# mobo_v1_1_6-20-18.net
KiCad netlist of a schematic drawn in EAGLE
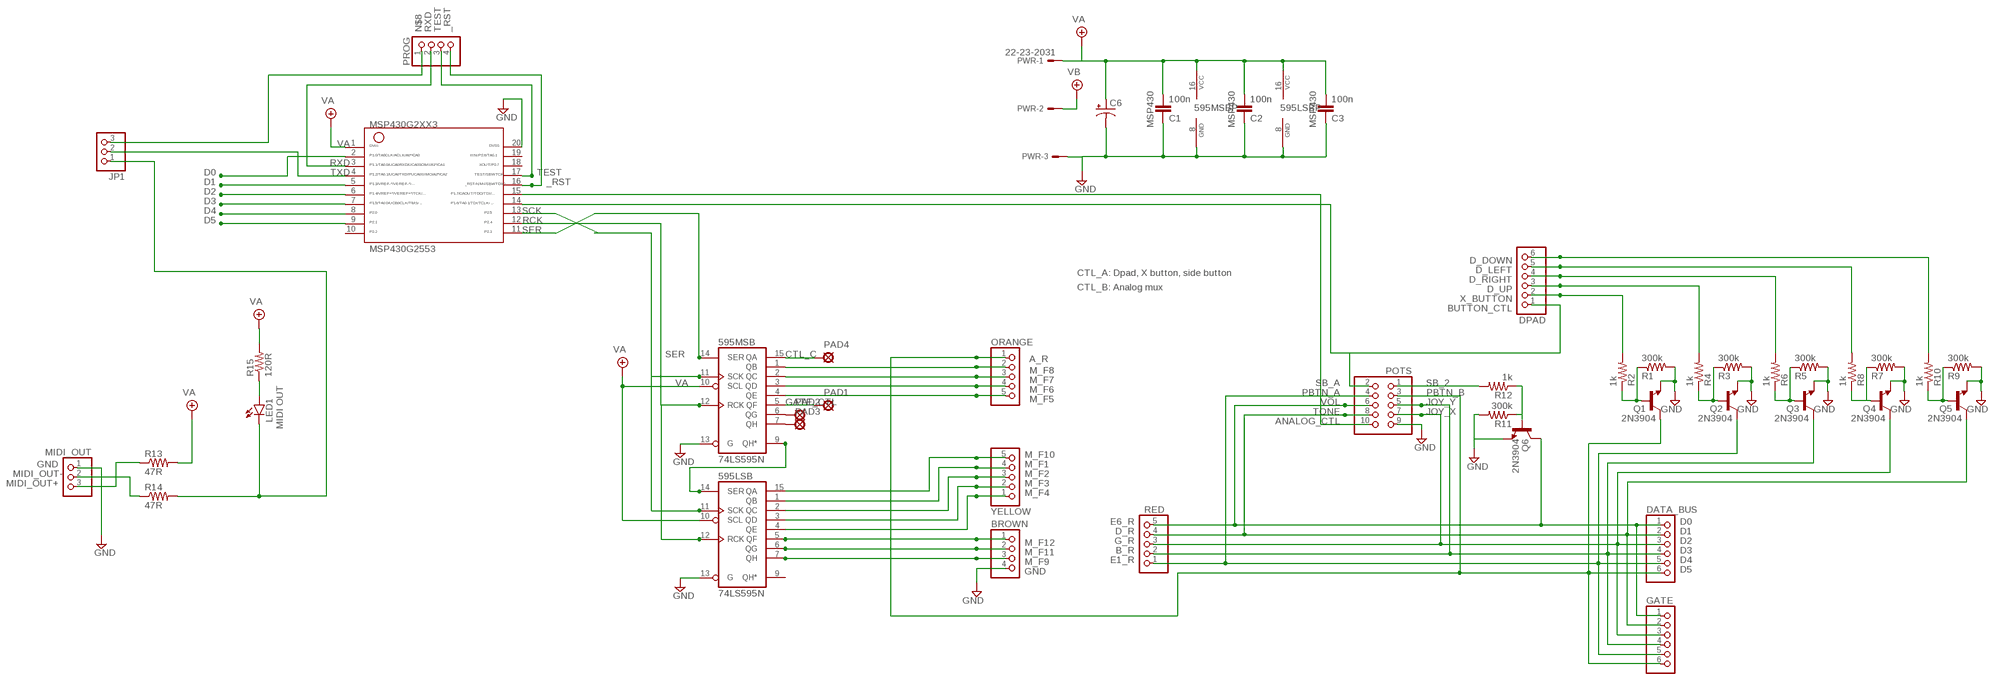
[diagram p0: schematic, sheet 1]

(export (version "E")
  (design (tool "Eeschema 10.0.6"))
  (components
    (comp (ref "595LSB")
      (value "74LS595N")
      (footprint "eagle-import:DIL16")
      (libsource (lib "eagle-import") (part "74595NLS"))
    )
    (comp (ref "595MSB")
      (value "74LS595N")
      (footprint "eagle-import:DIL16")
      (libsource (lib "eagle-import") (part "74595NLS"))
    )
    (comp (ref "BROWN")
      (value "PINHD-1X4")
      (footprint "eagle-import:1X04")
      (libsource (lib "eagle-import") (part "PINHD-1X4"))
    )
    (comp (ref "C1")
      (value "100n")
      (footprint "eagle-import:050X030_050_3")
      (libsource (lib "eagle-import") (part "050X030_050"))
    )
    (comp (ref "C2")
      (value "100n")
      (footprint "eagle-import:050X030_050_3")
      (libsource (lib "eagle-import") (part "050X030_050"))
    )
    (comp (ref "C3")
      (value "100n")
      (footprint "eagle-import:050X030_050_3")
      (libsource (lib "eagle-import") (part "050X030_050"))
    )
    (comp (ref "C6")
      (value "0501")
      (footprint "eagle-import:050_020_1")
      (libsource (lib "eagle-import") (part "0501"))
    )
    (comp (ref "DATA_BUS")
      (value "PINHD-1X6")
      (footprint "eagle-import:1X06")
      (libsource (lib "eagle-import") (part "PINHD-1X6"))
    )
    (comp (ref "DPAD")
      (value "PINHD-1X6")
      (footprint "eagle-import:1X06")
      (libsource (lib "eagle-import") (part "PINHD-1X6"))
    )
    (comp (ref "GATE")
      (value "PINHD-1X6")
      (footprint "eagle-import:1X06")
      (libsource (lib "eagle-import") (part "PINHD-1X6"))
    )
    (comp (ref "JP1")
      (value "PINHD-1X3")
      (footprint "eagle-import:1X03")
      (libsource (lib "eagle-import") (part "PINHD-1X3"))
    )
    (comp (ref "LED1")
      (value "LED3MM")
      (footprint "eagle-import:LED3MM")
      (libsource (lib "eagle-import") (part "LED3MM"))
    )
    (comp (ref "MIDI_OUT")
      (value "PINHD-1X3")
      (footprint "eagle-import:1X03")
      (libsource (lib "eagle-import") (part "PINHD-1X3"))
    )
    (comp (ref "MSP430G2553")
      (value "G2XX3---N20")
      (footprint "eagle-import:N20")
      (libsource (lib "eagle-import") (part "G2XX3---N20"))
    )
    (comp (ref "ORANGE")
      (value "PINHD-1X5")
      (footprint "eagle-import:1X05")
      (libsource (lib "eagle-import") (part "PINHD-1X5"))
    )
    (comp (ref "PAD1")
      (value "PAD")
      (footprint "eagle-import:SQUARE")
      (libsource (lib "eagle-import") (part "PAD"))
    )
    (comp (ref "PAD2")
      (value "PAD")
      (footprint "eagle-import:SQUARE")
      (libsource (lib "eagle-import") (part "PAD"))
    )
    (comp (ref "PAD3")
      (value "PAD")
      (footprint "eagle-import:SQUARE")
      (libsource (lib "eagle-import") (part "PAD"))
    )
    (comp (ref "PAD4")
      (value "PAD")
      (footprint "eagle-import:SQUARE")
      (libsource (lib "eagle-import") (part "PAD"))
    )
    (comp (ref "POTS")
      (value "PINHD-2X5")
      (footprint "eagle-import:2X05")
      (libsource (lib "eagle-import") (part "PINHD-2X5"))
    )
    (comp (ref "PROG")
      (value "PINHD-1X4")
      (footprint "eagle-import:1X04")
      (libsource (lib "eagle-import") (part "PINHD-1X4"))
    )
    (comp (ref "PWR")
      (value "22-23-2031")
      (footprint "eagle-import:22-23-2031")
      (fields (field (name "MF") "MOLEX"))
      (libsource (lib "eagle-import") (part "22-23-2031"))
    )
    (comp (ref "Q1")
      (value "2N3904")
      (footprint "eagle-import:TO92-")
      (libsource (lib "eagle-import") (part "2N3904"))
    )
    (comp (ref "Q2")
      (value "2N3904")
      (footprint "eagle-import:TO92-")
      (libsource (lib "eagle-import") (part "2N3904"))
    )
    (comp (ref "Q3")
      (value "2N3904")
      (footprint "eagle-import:TO92-")
      (libsource (lib "eagle-import") (part "2N3904"))
    )
    (comp (ref "Q4")
      (value "2N3904")
      (footprint "eagle-import:TO92-")
      (libsource (lib "eagle-import") (part "2N3904"))
    )
    (comp (ref "Q5")
      (value "2N3904")
      (footprint "eagle-import:TO92-")
      (libsource (lib "eagle-import") (part "2N3904"))
    )
    (comp (ref "Q6")
      (value "2N3904")
      (footprint "eagle-import:TO92-")
      (libsource (lib "eagle-import") (part "2N3904"))
    )
    (comp (ref "R1")
      (value "300k")
      (footprint "eagle-import:R0207_3")
      (libsource (lib "eagle-import") (part "6MM.3"))
    )
    (comp (ref "R2")
      (value "1k")
      (footprint "eagle-import:R0207_3")
      (libsource (lib "eagle-import") (part "6MM.3"))
    )
    (comp (ref "R3")
      (value "300k")
      (footprint "eagle-import:R0207_3")
      (libsource (lib "eagle-import") (part "6MM.3"))
    )
    (comp (ref "R4")
      (value "1k")
      (footprint "eagle-import:R0207_3")
      (libsource (lib "eagle-import") (part "6MM.3"))
    )
    (comp (ref "R5")
      (value "300k")
      (footprint "eagle-import:R0207_3")
      (libsource (lib "eagle-import") (part "6MM.3"))
    )
    (comp (ref "R6")
      (value "1k")
      (footprint "eagle-import:R0207_3")
      (libsource (lib "eagle-import") (part "6MM.3"))
    )
    (comp (ref "R7")
      (value "300k")
      (footprint "eagle-import:R0207_3")
      (libsource (lib "eagle-import") (part "6MM.3"))
    )
    (comp (ref "R8")
      (value "1k")
      (footprint "eagle-import:R0207_3")
      (libsource (lib "eagle-import") (part "6MM.3"))
    )
    (comp (ref "R9")
      (value "300k")
      (footprint "eagle-import:R0207_3")
      (libsource (lib "eagle-import") (part "6MM.3"))
    )
    (comp (ref "R10")
      (value "1k")
      (footprint "eagle-import:R0207_3")
      (libsource (lib "eagle-import") (part "6MM.3"))
    )
    (comp (ref "R11")
      (value "300k")
      (footprint "eagle-import:R0207_3")
      (libsource (lib "eagle-import") (part "6MM.3"))
    )
    (comp (ref "R12")
      (value "1k")
      (footprint "eagle-import:R0207_3")
      (libsource (lib "eagle-import") (part "6MM.3"))
    )
    (comp (ref "R13")
      (value "47R")
      (footprint "eagle-import:R0207_3")
      (libsource (lib "eagle-import") (part "6MM.3"))
    )
    (comp (ref "R14")
      (value "47R")
      (footprint "eagle-import:R0207_3")
      (libsource (lib "eagle-import") (part "6MM.3"))
    )
    (comp (ref "R15")
      (value "120R")
      (footprint "eagle-import:R0207_3")
      (libsource (lib "eagle-import") (part "6MM.3"))
    )
    (comp (ref "RED")
      (value "PINHD-1X5")
      (footprint "eagle-import:1X05")
      (libsource (lib "eagle-import") (part "PINHD-1X5"))
    )
    (comp (ref "YELLOW")
      (value "PINHD-1X5")
      (footprint "eagle-import:1X05")
      (libsource (lib "eagle-import") (part "PINHD-1X5"))
    )
  )
  (nets
    (net (code "1") (name "/ANALOG_CTL") (class "Default")
      (node (ref "MSP430G2553") (pin "15") (pinfunction "15_15") (pintype "bidirectional"))
      (node (ref "POTS") (pin "10") (pinfunction "10_10") (pintype "passive"))
    )
    (net (code "2") (name "/BUTTON_CTL") (class "Default")
      (node (ref "DPAD") (pin "1") (pinfunction "1_1") (pintype "passive"))
      (node (ref "MSP430G2553") (pin "14") (pinfunction "14_14") (pintype "bidirectional"))
      (node (ref "POTS") (pin "2") (pinfunction "2_2") (pintype "passive"))
    )
    (net (code "3") (name "/CTL_C") (class "Default")
      (node (ref "595MSB") (pin "15") (pinfunction "QA_15") (pintype "tri_state"))
      (node (ref "PAD4") (pin "1") (pinfunction "PAD_1") (pintype "passive"))
    )
    (net (code "4") (name "/D0") (class "Default")
      (node (ref "DATA_BUS") (pin "1") (pinfunction "1_1") (pintype "passive"))
      (node (ref "GATE") (pin "1") (pinfunction "1_1") (pintype "passive"))
      (node (ref "MSP430G2553") (pin "2") (pinfunction "2_2") (pintype "bidirectional"))
      (node (ref "POTS") (pin "6") (pinfunction "6_6") (pintype "passive"))
      (node (ref "Q6") (pin "1") (pinfunction "C_1") (pintype "passive"))
      (node (ref "RED") (pin "5") (pinfunction "5_5") (pintype "passive"))
    )
    (net (code "5") (name "/D1") (class "Default")
      (node (ref "DATA_BUS") (pin "2") (pinfunction "2_2") (pintype "passive"))
      (node (ref "GATE") (pin "2") (pinfunction "2_2") (pintype "passive"))
      (node (ref "MSP430G2553") (pin "5") (pinfunction "5_5") (pintype "bidirectional"))
      (node (ref "POTS") (pin "8") (pinfunction "8_8") (pintype "passive"))
      (node (ref "Q5") (pin "1") (pinfunction "C_1") (pintype "passive"))
      (node (ref "RED") (pin "4") (pinfunction "4_4") (pintype "passive"))
    )
    (net (code "6") (name "/D2") (class "Default")
      (node (ref "DATA_BUS") (pin "3") (pinfunction "3_3") (pintype "passive"))
      (node (ref "GATE") (pin "3") (pinfunction "3_3") (pintype "passive"))
      (node (ref "MSP430G2553") (pin "6") (pinfunction "6_6") (pintype "bidirectional"))
      (node (ref "POTS") (pin "7") (pinfunction "7_7") (pintype "passive"))
      (node (ref "Q4") (pin "1") (pinfunction "C_1") (pintype "passive"))
      (node (ref "RED") (pin "3") (pinfunction "3_3") (pintype "passive"))
    )
    (net (code "7") (name "/D3") (class "Default")
      (node (ref "DATA_BUS") (pin "4") (pinfunction "4_4") (pintype "passive"))
      (node (ref "GATE") (pin "4") (pinfunction "4_4") (pintype "passive"))
      (node (ref "MSP430G2553") (pin "7") (pinfunction "7_7") (pintype "bidirectional"))
      (node (ref "POTS") (pin "5") (pinfunction "5_5") (pintype "passive"))
      (node (ref "Q3") (pin "1") (pinfunction "C_1") (pintype "passive"))
      (node (ref "RED") (pin "2") (pinfunction "2_2") (pintype "passive"))
    )
    (net (code "8") (name "/D4") (class "Default")
      (node (ref "DATA_BUS") (pin "5") (pinfunction "5_5") (pintype "passive"))
      (node (ref "GATE") (pin "5") (pinfunction "5_5") (pintype "passive"))
      (node (ref "MSP430G2553") (pin "8") (pinfunction "8_8") (pintype "bidirectional"))
      (node (ref "POTS") (pin "4") (pinfunction "4_4") (pintype "passive"))
      (node (ref "Q2") (pin "1") (pinfunction "C_1") (pintype "passive"))
      (node (ref "RED") (pin "1") (pinfunction "1_1") (pintype "passive"))
    )
    (net (code "9") (name "/D5") (class "Default")
      (node (ref "DATA_BUS") (pin "6") (pinfunction "6_6") (pintype "passive"))
      (node (ref "GATE") (pin "6") (pinfunction "6_6") (pintype "passive"))
      (node (ref "MSP430G2553") (pin "9") (pinfunction "9_9") (pintype "bidirectional"))
      (node (ref "ORANGE") (pin "1") (pinfunction "1_1") (pintype "passive"))
      (node (ref "POTS") (pin "3") (pinfunction "3_3") (pintype "passive"))
      (node (ref "Q1") (pin "1") (pinfunction "C_1") (pintype "passive"))
    )
    (net (code "10") (name "/D_DOWN") (class "Default")
      (node (ref "DPAD") (pin "6") (pinfunction "6_6") (pintype "passive"))
      (node (ref "R10") (pin "2") (pinfunction "2_2") (pintype "passive"))
    )
    (net (code "11") (name "/D_LEFT") (class "Default")
      (node (ref "DPAD") (pin "5") (pinfunction "5_5") (pintype "passive"))
      (node (ref "R8") (pin "2") (pinfunction "2_2") (pintype "passive"))
    )
    (net (code "12") (name "/D_RIGHT") (class "Default")
      (node (ref "DPAD") (pin "4") (pinfunction "4_4") (pintype "passive"))
      (node (ref "R6") (pin "2") (pinfunction "2_2") (pintype "passive"))
    )
    (net (code "13") (name "/D_UP") (class "Default")
      (node (ref "DPAD") (pin "3") (pinfunction "3_3") (pintype "passive"))
      (node (ref "R4") (pin "2") (pinfunction "2_2") (pintype "passive"))
    )
    (net (code "14") (name "/GATE_CTL") (class "Default")
      (node (ref "595MSB") (pin "5") (pinfunction "QF_5") (pintype "tri_state"))
      (node (ref "PAD1") (pin "1") (pinfunction "PAD_1") (pintype "passive"))
    )
    (net (code "15") (name "/MIDI_OUT+") (class "Default")
      (node (ref "MIDI_OUT") (pin "3") (pinfunction "3_3") (pintype "passive"))
      (node (ref "R13") (pin "1") (pinfunction "1_1") (pintype "passive"))
    )
    (net (code "16") (name "/MIDI_OUT-") (class "Default")
      (node (ref "MIDI_OUT") (pin "2") (pinfunction "2_2") (pintype "passive"))
      (node (ref "R14") (pin "1") (pinfunction "1_1") (pintype "passive"))
    )
    (net (code "17") (name "/M_F1") (class "Default")
      (node (ref "595LSB") (pin "1") (pinfunction "QB_1") (pintype "tri_state"))
      (node (ref "YELLOW") (pin "4") (pinfunction "4_4") (pintype "passive"))
    )
    (net (code "18") (name "/M_F2") (class "Default")
      (node (ref "595LSB") (pin "2") (pinfunction "QC_2") (pintype "tri_state"))
      (node (ref "YELLOW") (pin "3") (pinfunction "3_3") (pintype "passive"))
    )
    (net (code "19") (name "/M_F3") (class "Default")
      (node (ref "595LSB") (pin "3") (pinfunction "QD_3") (pintype "tri_state"))
      (node (ref "YELLOW") (pin "2") (pinfunction "2_2") (pintype "passive"))
    )
    (net (code "20") (name "/M_F4") (class "Default")
      (node (ref "595LSB") (pin "4") (pinfunction "QE_4") (pintype "tri_state"))
      (node (ref "YELLOW") (pin "1") (pinfunction "1_1") (pintype "passive"))
    )
    (net (code "21") (name "/M_F5") (class "Default")
      (node (ref "595MSB") (pin "4") (pinfunction "QE_4") (pintype "tri_state"))
      (node (ref "ORANGE") (pin "5") (pinfunction "5_5") (pintype "passive"))
    )
    (net (code "22") (name "/M_F6") (class "Default")
      (node (ref "595MSB") (pin "3") (pinfunction "QD_3") (pintype "tri_state"))
      (node (ref "ORANGE") (pin "4") (pinfunction "4_4") (pintype "passive"))
    )
    (net (code "23") (name "/M_F7") (class "Default")
      (node (ref "595MSB") (pin "2") (pinfunction "QC_2") (pintype "tri_state"))
      (node (ref "ORANGE") (pin "3") (pinfunction "3_3") (pintype "passive"))
    )
    (net (code "24") (name "/M_F8") (class "Default")
      (node (ref "595MSB") (pin "1") (pinfunction "QB_1") (pintype "tri_state"))
      (node (ref "ORANGE") (pin "2") (pinfunction "2_2") (pintype "passive"))
    )
    (net (code "25") (name "/M_F9") (class "Default")
      (node (ref "595LSB") (pin "7") (pinfunction "QH_7") (pintype "tri_state"))
      (node (ref "BROWN") (pin "3") (pinfunction "3_3") (pintype "passive"))
    )
    (net (code "26") (name "/M_F10") (class "Default")
      (node (ref "595LSB") (pin "15") (pinfunction "QA_15") (pintype "tri_state"))
      (node (ref "YELLOW") (pin "5") (pinfunction "5_5") (pintype "passive"))
    )
    (net (code "27") (name "/M_F11") (class "Default")
      (node (ref "595LSB") (pin "6") (pinfunction "QG_6") (pintype "tri_state"))
      (node (ref "BROWN") (pin "2") (pinfunction "2_2") (pintype "passive"))
    )
    (net (code "28") (name "/M_F12") (class "Default")
      (node (ref "595LSB") (pin "5") (pinfunction "QF_5") (pintype "tri_state"))
      (node (ref "BROWN") (pin "1") (pinfunction "1_1") (pintype "passive"))
    )
    (net (code "29") (name "/N$8") (class "Default")
      (node (ref "JP1") (pin "3") (pinfunction "3_3") (pintype "passive"))
      (node (ref "PROG") (pin "1") (pinfunction "1_1") (pintype "passive"))
    )
    (net (code "30") (name "/RCK") (class "Default")
      (node (ref "595LSB") (pin "12") (pinfunction "RCK_12") (pintype "input"))
      (node (ref "595MSB") (pin "12") (pinfunction "RCK_12") (pintype "input"))
      (node (ref "MSP430G2553") (pin "12") (pinfunction "12_12") (pintype "bidirectional"))
    )
    (net (code "31") (name "/RXD") (class "Default")
      (node (ref "MSP430G2553") (pin "3") (pinfunction "3_3") (pintype "bidirectional"))
      (node (ref "PROG") (pin "2") (pinfunction "2_2") (pintype "passive"))
    )
    (net (code "32") (name "/SB_2") (class "Default")
      (node (ref "POTS") (pin "1") (pinfunction "1_1") (pintype "passive"))
      (node (ref "R12") (pin "2") (pinfunction "2_2") (pintype "passive"))
    )
    (net (code "33") (name "/SCK") (class "Default")
      (node (ref "595LSB") (pin "11") (pinfunction "SCK_11") (pintype "input"))
      (node (ref "595MSB") (pin "11") (pinfunction "SCK_11") (pintype "input"))
      (node (ref "MSP430G2553") (pin "13") (pinfunction "13_13") (pintype "bidirectional"))
    )
    (net (code "34") (name "/SER") (class "Default")
      (node (ref "595MSB") (pin "14") (pinfunction "SER_14") (pintype "input"))
      (node (ref "MSP430G2553") (pin "11") (pinfunction "11_11") (pintype "bidirectional"))
    )
    (net (code "35") (name "/TEST") (class "Default")
      (node (ref "MSP430G2553") (pin "17") (pinfunction "17_17") (pintype "bidirectional"))
      (node (ref "PROG") (pin "3") (pinfunction "3_3") (pintype "passive"))
    )
    (net (code "36") (name "/TXD") (class "Default")
      (node (ref "JP1") (pin "2") (pinfunction "2_2") (pintype "passive"))
      (node (ref "MSP430G2553") (pin "4") (pinfunction "4_4") (pintype "bidirectional"))
    )
    (net (code "37") (name "/X_BUTTON") (class "Default")
      (node (ref "DPAD") (pin "2") (pinfunction "2_2") (pintype "passive"))
      (node (ref "R2") (pin "2") (pinfunction "2_2") (pintype "passive"))
    )
    (net (code "38") (name "/_RST") (class "Default")
      (node (ref "MSP430G2553") (pin "16") (pinfunction "16_16") (pintype "bidirectional"))
      (node (ref "PROG") (pin "4") (pinfunction "4_4") (pintype "passive"))
    )
    (net (code "39") (name "GND") (class "Default")
      (node (ref "595LSB") (pin "13") (pinfunction "G_13") (pintype "input"))
      (node (ref "595LSB") (pin "8") (pinfunction "GND_8") (pintype "power_in"))
      (node (ref "595MSB") (pin "13") (pinfunction "G_13") (pintype "input"))
      (node (ref "595MSB") (pin "8") (pinfunction "GND_8") (pintype "power_in"))
      (node (ref "BROWN") (pin "4") (pinfunction "4_4") (pintype "passive"))
      (node (ref "C1") (pin "1") (pinfunction "1_1") (pintype "passive"))
      (node (ref "C2") (pin "1") (pinfunction "1_1") (pintype "passive"))
      (node (ref "C3") (pin "1") (pinfunction "1_1") (pintype "passive"))
      (node (ref "C6") (pin "-") (pinfunction "-_-") (pintype "passive"))
      (node (ref "MIDI_OUT") (pin "1") (pinfunction "1_1") (pintype "passive"))
      (node (ref "MSP430G2553") (pin "20") (pinfunction "20_20") (pintype "bidirectional"))
      (node (ref "POTS") (pin "9") (pinfunction "9_9") (pintype "passive"))
      (node (ref "PWR") (pin "3") (pinfunction "S_3") (pintype "passive"))
      (node (ref "Q1") (pin "3") (pinfunction "E_3") (pintype "passive"))
      (node (ref "Q2") (pin "3") (pinfunction "E_3") (pintype "passive"))
      (node (ref "Q3") (pin "3") (pinfunction "E_3") (pintype "passive"))
      (node (ref "Q4") (pin "3") (pinfunction "E_3") (pintype "passive"))
      (node (ref "Q5") (pin "3") (pinfunction "E_3") (pintype "passive"))
      (node (ref "Q6") (pin "3") (pinfunction "E_3") (pintype "passive"))
      (node (ref "R1") (pin "2") (pinfunction "2_2") (pintype "passive"))
      (node (ref "R11") (pin "2") (pinfunction "2_2") (pintype "passive"))
      (node (ref "R3") (pin "2") (pinfunction "2_2") (pintype "passive"))
      (node (ref "R5") (pin "2") (pinfunction "2_2") (pintype "passive"))
      (node (ref "R7") (pin "2") (pinfunction "2_2") (pintype "passive"))
      (node (ref "R9") (pin "2") (pinfunction "2_2") (pintype "passive"))
    )
    (net (code "40") (name "Net-(595LSBA-SER)") (class "Default")
      (node (ref "595LSB") (pin "14") (pinfunction "SER_14") (pintype "input"))
      (node (ref "595MSB") (pin "9") (pinfunction "QH*_9") (pintype "tri_state"))
    )
    (net (code "41") (name "Net-(595MSBA-QG)") (class "Default")
      (node (ref "595MSB") (pin "6") (pinfunction "QG_6") (pintype "tri_state"))
      (node (ref "PAD2") (pin "1") (pinfunction "PAD_1") (pintype "passive"))
    )
    (net (code "42") (name "Net-(595MSBA-QH)") (class "Default")
      (node (ref "595MSB") (pin "7") (pinfunction "QH_7") (pintype "tri_state"))
      (node (ref "PAD3") (pin "1") (pinfunction "PAD_1") (pintype "passive"))
    )
    (net (code "43") (name "Net-(LED1-C)") (class "Default")
      (node (ref "JP1") (pin "1") (pinfunction "1_1") (pintype "passive"))
      (node (ref "LED1") (pin "K") (pinfunction "C_K") (pintype "passive"))
      (node (ref "R14") (pin "2") (pinfunction "2_2") (pintype "passive"))
    )
    (net (code "44") (name "Net-(LED1-PadA)") (class "Default")
      (node (ref "LED1") (pin "A") (pinfunction "A_A") (pintype "passive"))
      (node (ref "R15") (pin "1") (pinfunction "1_1") (pintype "passive"))
    )
    (net (code "45") (name "Net-(Q1-B)") (class "Default")
      (node (ref "Q1") (pin "2") (pinfunction "B_2") (pintype "passive"))
      (node (ref "R1") (pin "1") (pinfunction "1_1") (pintype "passive"))
      (node (ref "R2") (pin "1") (pinfunction "1_1") (pintype "passive"))
    )
    (net (code "46") (name "Net-(Q2-B)") (class "Default")
      (node (ref "Q2") (pin "2") (pinfunction "B_2") (pintype "passive"))
      (node (ref "R3") (pin "1") (pinfunction "1_1") (pintype "passive"))
      (node (ref "R4") (pin "1") (pinfunction "1_1") (pintype "passive"))
    )
    (net (code "47") (name "Net-(Q3-B)") (class "Default")
      (node (ref "Q3") (pin "2") (pinfunction "B_2") (pintype "passive"))
      (node (ref "R5") (pin "1") (pinfunction "1_1") (pintype "passive"))
      (node (ref "R6") (pin "1") (pinfunction "1_1") (pintype "passive"))
    )
    (net (code "48") (name "Net-(Q4-B)") (class "Default")
      (node (ref "Q4") (pin "2") (pinfunction "B_2") (pintype "passive"))
      (node (ref "R7") (pin "1") (pinfunction "1_1") (pintype "passive"))
      (node (ref "R8") (pin "1") (pinfunction "1_1") (pintype "passive"))
    )
    (net (code "49") (name "Net-(Q5-B)") (class "Default")
      (node (ref "Q5") (pin "2") (pinfunction "B_2") (pintype "passive"))
      (node (ref "R10") (pin "1") (pinfunction "1_1") (pintype "passive"))
      (node (ref "R9") (pin "1") (pinfunction "1_1") (pintype "passive"))
    )
    (net (code "50") (name "Net-(Q6-B)") (class "Default")
      (node (ref "Q6") (pin "2") (pinfunction "B_2") (pintype "passive"))
      (node (ref "R11") (pin "1") (pinfunction "1_1") (pintype "passive"))
      (node (ref "R12") (pin "1") (pinfunction "1_1") (pintype "passive"))
    )
    (net (code "51") (name "VA") (class "Default")
      (node (ref "595LSB") (pin "10") (pinfunction "SCL_10") (pintype "input"))
      (node (ref "595LSB") (pin "16") (pinfunction "VCC_16") (pintype "power_in"))
      (node (ref "595MSB") (pin "10") (pinfunction "SCL_10") (pintype "input"))
      (node (ref "595MSB") (pin "16") (pinfunction "VCC_16") (pintype "power_in"))
      (node (ref "C1") (pin "2") (pinfunction "2_2") (pintype "passive"))
      (node (ref "C2") (pin "2") (pinfunction "2_2") (pintype "passive"))
      (node (ref "C3") (pin "2") (pinfunction "2_2") (pintype "passive"))
      (node (ref "C6") (pin "+") (pinfunction "+_+") (pintype "passive"))
      (node (ref "MSP430G2553") (pin "1") (pinfunction "1_1") (pintype "bidirectional"))
      (node (ref "PWR") (pin "1") (pinfunction "S_1") (pintype "passive"))
      (node (ref "R13") (pin "2") (pinfunction "2_2") (pintype "passive"))
      (node (ref "R15") (pin "2") (pinfunction "2_2") (pintype "passive"))
    )
    (net (code "52") (name "VB") (class "Default")
      (node (ref "PWR") (pin "2") (pinfunction "S_2") (pintype "passive"))
    )
    (net (code "53") (name "unconnected-(595LSBA-QH*-Pad9)") (class "Default")
      (node (ref "595LSB") (pin "9") (pinfunction "QH*_9") (pintype "tri_state"))
    )
    (net (code "54") (name "unconnected-(MSP430G2553-Pad10)") (class "Default")
      (node (ref "MSP430G2553") (pin "10") (pinfunction "10_10") (pintype "bidirectional"))
    )
    (net (code "55") (name "unconnected-(MSP430G2553-Pad18)") (class "Default")
      (node (ref "MSP430G2553") (pin "18") (pinfunction "18_18") (pintype "bidirectional"))
    )
    (net (code "56") (name "unconnected-(MSP430G2553-Pad19)") (class "Default")
      (node (ref "MSP430G2553") (pin "19") (pinfunction "19_19") (pintype "bidirectional"))
    )
  )
)
